# Esquematico_2022-08-20.net
KiCad netlist of a schematic drawn in Altium Designer
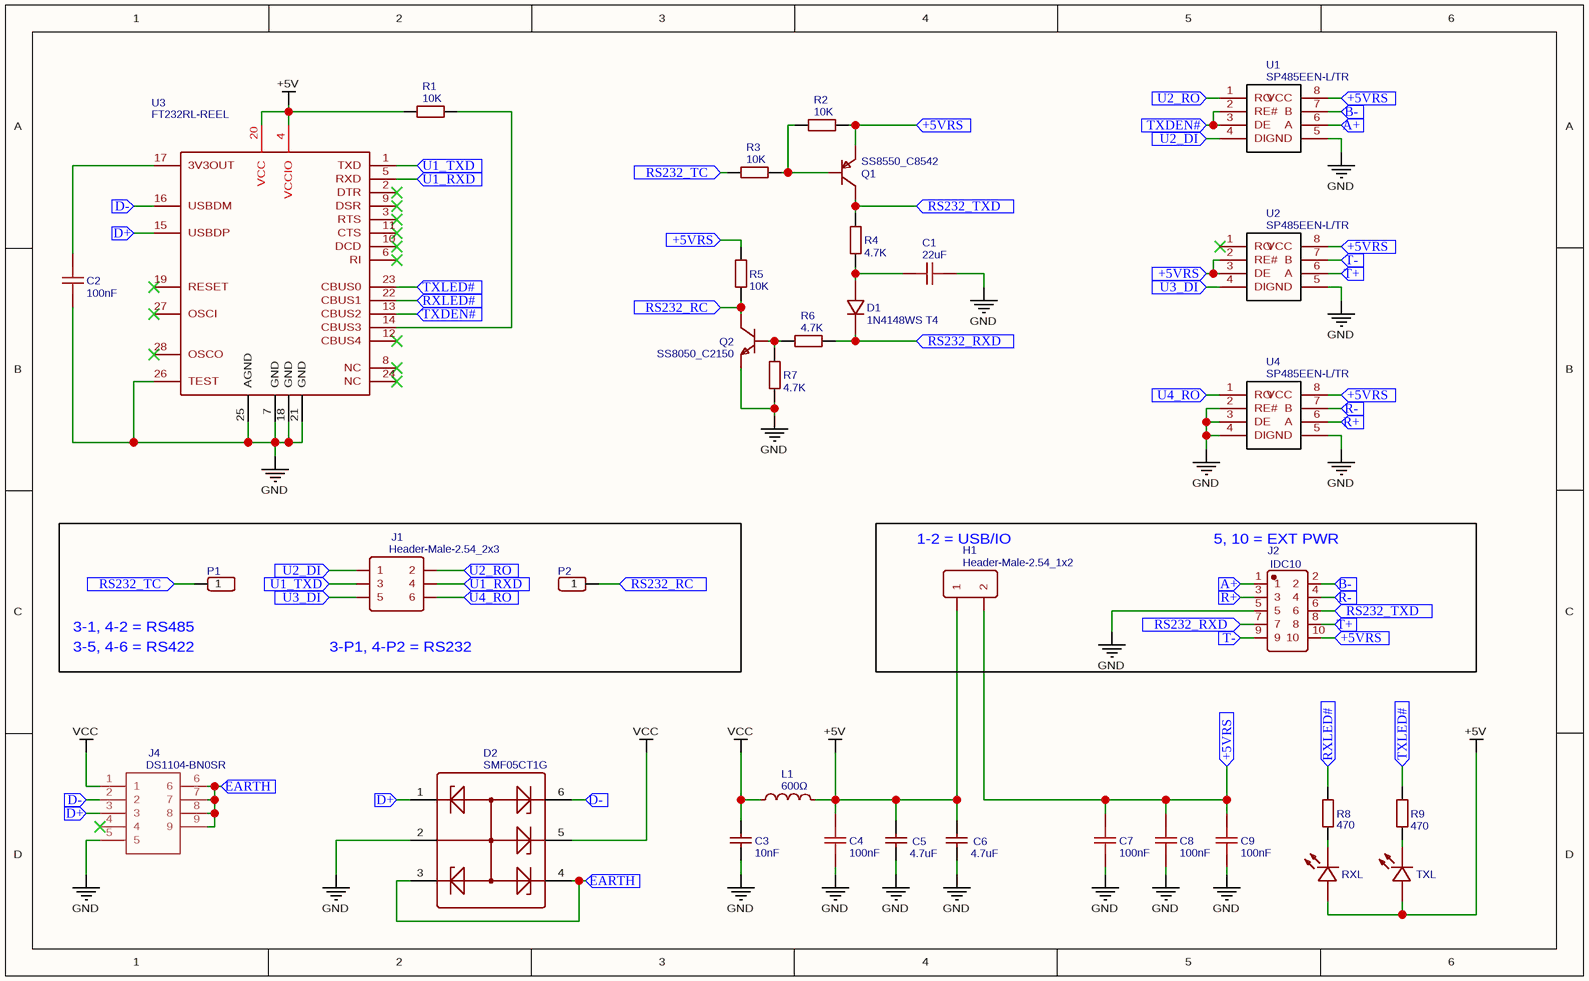
[diagram p0: Esquematico_2022-08-20.schdoc]

(export (version "E")
  (design (tool "Eeschema 10.0.6"))
  (components
    (comp (ref "C1")
      (value "22uF")
      (fields
        (field (name "BOM_MANUFACTURER PART") "CL21A226MAQNNNE")
        (field (name "BOM_SUPPLIER PART") "C45783")
      )
      (libsource (lib "altium-import") (part "root_0_22uF_"))
    )
    (comp (ref "C2")
      (value "100nF")
      (fields
        (field (name "BOM_MANUFACTURER PART") "CC0603KRX7R9BB104")
        (field (name "BOM_SUPPLIER PART") "C14663")
      )
      (libsource (lib "altium-import") (part "root_1_100nF_"))
    )
    (comp (ref "C3")
      (value "10nF")
      (fields
        (field (name "BOM_MANUFACTURER PART") "0603B103K500NT")
        (field (name "BOM_SUPPLIER PART") "C57112")
      )
      (libsource (lib "altium-import") (part "root_1_10nF_"))
    )
    (comp (ref "C4")
      (value "100nF")
      (fields
        (field (name "BOM_MANUFACTURER PART") "CC0603KRX7R9BB104")
        (field (name "BOM_SUPPLIER PART") "C14663")
      )
      (libsource (lib "altium-import") (part "root_1_100nF_"))
    )
    (comp (ref "C5")
      (value "4.7uF")
      (fields
        (field (name "BOM_MANUFACTURER PART") "CL10A475KO8NNNC")
        (field (name "BOM_SUPPLIER PART") "C19666")
      )
      (libsource (lib "altium-import") (part "root_1_4.7uF_"))
    )
    (comp (ref "C6")
      (value "4.7uF")
      (fields
        (field (name "BOM_MANUFACTURER PART") "CL10A475KO8NNNC")
        (field (name "BOM_SUPPLIER PART") "C19666")
      )
      (libsource (lib "altium-import") (part "root_1_4.7uF_"))
    )
    (comp (ref "C7")
      (value "100nF")
      (fields
        (field (name "BOM_MANUFACTURER PART") "CC0603KRX7R9BB104")
        (field (name "BOM_SUPPLIER PART") "C14663")
      )
      (libsource (lib "altium-import") (part "root_1_100nF_"))
    )
    (comp (ref "C8")
      (value "100nF")
      (fields
        (field (name "BOM_MANUFACTURER PART") "CC0603KRX7R9BB104")
        (field (name "BOM_SUPPLIER PART") "C14663")
      )
      (libsource (lib "altium-import") (part "root_1_100nF_"))
    )
    (comp (ref "C9")
      (value "100nF")
      (fields
        (field (name "BOM_MANUFACTURER PART") "CC0603KRX7R9BB104")
        (field (name "BOM_SUPPLIER PART") "C14663")
      )
      (libsource (lib "altium-import") (part "root_1_100nF_"))
    )
    (comp (ref "D1")
      (value "1N4148WS T4")
      (fields (field (name "BOM_SUPPLIER PART") "C2128"))
      (libsource (lib "altium-import") (part "root_1_1N4148WS T4_"))
    )
    (comp (ref "D2")
      (value "SMF05CT1G")
      (fields (field (name "BOM_SUPPLIER PART") "C15879"))
      (libsource (lib "altium-import") (part "root_0_SMF05CT1G_"))
    )
    (comp (ref "H1")
      (value "Header-Male-2.54_1x2")
      (fields (field (name "BOM_MANUFACTURER PART") "826629-2") (field (name "BOM_SUPPLIER PART") "C86471"))
      (libsource (lib "altium-import") (part "root_1_Header-Male-2.54_1x2_"))
    )
    (comp (ref "J1")
      (value "Header-Male-2.54_2x3")
      (fields (field (name "BOM_SUPPLIER PART") "C65114"))
      (libsource (lib "altium-import") (part "root_0_Header-Male-2.54_2x3_"))
    )
    (comp (ref "J2")
      (value "IDC10")
      (fields (field (name "CONTRIBUTOR") "romanlee"))
      (libsource (lib "altium-import") (part "root_0_IDC10_"))
    )
    (comp (ref "J4")
      (value "DS1104-BN0SR")
      (fields (field (name "CONTRIBUTOR") "kutsiarda"))
      (libsource (lib "altium-import") (part "root_0_DS1104-BN0SR_"))
    )
    (comp (ref "L1")
      (value "600Ω")
      (fields
        (field (name "BOM_MANUFACTURER PART") "GZ2012D601TF")
        (field (name "BOM_SUPPLIER PART") "C1017")
      )
      (libsource (lib "altium-import") (part "root_0_600Ω_"))
    )
    (comp (ref "P1")
      (value "Header-Male-2.54_1x1")
      (fields (field (name "BOM_SUPPLIER PART") "C81276"))
      (libsource (lib "altium-import") (part "root_0_Header-Male-2.54_1x1_"))
    )
    (comp (ref "P2")
      (value "Header-Male-2.54_1x1")
      (fields (field (name "BOM_SUPPLIER PART") "C81276"))
      (libsource (lib "altium-import") (part "root_2_Header-Male-2.54_1x1_"))
    )
    (comp (ref "Q1")
      (value "SS8550_C8542")
      (fields (field (name "BOM_MANUFACTURER PART") "SS8550") (field (name "BOM_SUPPLIER PART") "C8542"))
      (libsource (lib "altium-import") (part "root_0_SS8550_C8542_"))
    )
    (comp (ref "Q2")
      (value "SS8050_C2150")
      (fields (field (name "BOM_MANUFACTURER PART") "SS8050") (field (name "BOM_SUPPLIER PART") "C2150"))
      (libsource (lib "altium-import") (part "root_0_SS8050_C2150_"))
    )
    (comp (ref "R1")
      (value "10K")
      (fields
        (field (name "BOM_MANUFACTURER PART") "0603WAF1002T5E")
        (field (name "BOM_SUPPLIER PART") "C25804")
      )
      (libsource (lib "altium-import") (part "root_0_10K_"))
    )
    (comp (ref "R2")
      (value "10K")
      (fields
        (field (name "BOM_MANUFACTURER PART") "0603WAF1002T5E")
        (field (name "BOM_SUPPLIER PART") "C25804")
      )
      (libsource (lib "altium-import") (part "root_0_10K_"))
    )
    (comp (ref "R3")
      (value "10K")
      (fields
        (field (name "BOM_MANUFACTURER PART") "0603WAF1002T5E")
        (field (name "BOM_SUPPLIER PART") "C25804")
      )
      (libsource (lib "altium-import") (part "root_0_10K_"))
    )
    (comp (ref "R4")
      (value "4.7K")
      (fields
        (field (name "BOM_MANUFACTURER PART") "0603WAF4701T5E")
        (field (name "BOM_SUPPLIER PART") "C23162")
      )
      (libsource (lib "altium-import") (part "root_1_4.7K_"))
    )
    (comp (ref "R5")
      (value "10K")
      (fields
        (field (name "BOM_MANUFACTURER PART") "0603WAF1002T5E")
        (field (name "BOM_SUPPLIER PART") "C25804")
      )
      (libsource (lib "altium-import") (part "root_1_10K_"))
    )
    (comp (ref "R6")
      (value "4.7K")
      (fields
        (field (name "BOM_MANUFACTURER PART") "0603WAF4701T5E")
        (field (name "BOM_SUPPLIER PART") "C23162")
      )
      (libsource (lib "altium-import") (part "root_2_4.7K_"))
    )
    (comp (ref "R7")
      (value "4.7K")
      (fields
        (field (name "BOM_MANUFACTURER PART") "0603WAF4701T5E")
        (field (name "BOM_SUPPLIER PART") "C23162")
      )
      (libsource (lib "altium-import") (part "root_3_4.7K_"))
    )
    (comp (ref "R8")
      (value "470")
      (fields
        (field (name "BOM_MANUFACTURER PART") "0603WAF4700T5E")
        (field (name "BOM_SUPPLIER PART") "C23179")
      )
      (libsource (lib "altium-import") (part "root_1_470_"))
    )
    (comp (ref "R9")
      (value "470")
      (fields
        (field (name "BOM_MANUFACTURER PART") "0603WAF4700T5E")
        (field (name "BOM_SUPPLIER PART") "C23179")
      )
      (libsource (lib "altium-import") (part "root_3_470_"))
    )
    (comp (ref "RXL")
      (value "RXL")
      (fields
        (field (name "BOM_MANUFACTURER PART") "0603White light")
        (field (name "BOM_SUPPLIER PART") "C2290")
      )
      (libsource (lib "altium-import") (part "root_1_RXL_"))
    )
    (comp (ref "TXL")
      (value "TXL")
      (fields (field (name "BOM_MANUFACTURER PART") "KT-0603R") (field (name "BOM_SUPPLIER PART") "C2286"))
      (libsource (lib "altium-import") (part "root_3_TXL_"))
    )
    (comp (ref "U1")
      (value "SP485EEN-L/TR")
      (fields (field (name "BOM_SUPPLIER PART") "C6855"))
      (libsource (lib "altium-import") (part "root_0_SP485EEN-L/TR_"))
    )
    (comp (ref "U2")
      (value "SP485EEN-L/TR")
      (fields (field (name "BOM_SUPPLIER PART") "C6855"))
      (libsource (lib "altium-import") (part "root_0_SP485EEN-L/TR_"))
    )
    (comp (ref "U3")
      (value "FT232RL-REEL")
      (fields (field (name "BOM_SUPPLIER PART") "C8690"))
      (libsource (lib "altium-import") (part "root_0_FT232RL-REEL_"))
    )
    (comp (ref "U4")
      (value "SP485EEN-L/TR")
      (fields (field (name "BOM_SUPPLIER PART") "C6855"))
      (libsource (lib "altium-import") (part "root_0_SP485EEN-L/TR_"))
    )
  )
  (nets
    (net (code "1") (name "+5V") (class "Default")
      (node (ref "C4") (pin "2") (pinfunction "2_2") (pintype "passive"))
      (node (ref "C5") (pin "2") (pinfunction "2_2") (pintype "passive"))
      (node (ref "C6") (pin "2") (pinfunction "2_2") (pintype "passive"))
      (node (ref "H1") (pin "1") (pinfunction "1_1") (pintype "passive"))
      (node (ref "L1") (pin "2") (pinfunction "2_2") (pintype "passive"))
      (node (ref "R1") (pin "1") (pinfunction "1_1") (pintype "passive"))
      (node (ref "RXL") (pin "1") (pinfunction "A_1") (pintype "passive"))
      (node (ref "TXL") (pin "1") (pinfunction "A_1") (pintype "passive"))
      (node (ref "U3") (pin "20") (pinfunction "VCC_20") (pintype "passive"))
      (node (ref "U3") (pin "4") (pinfunction "VCCIO_4") (pintype "passive"))
    )
    (net (code "2") (name "/+5VRS") (class "Default")
      (node (ref "C7") (pin "2") (pinfunction "2_2") (pintype "passive"))
      (node (ref "C8") (pin "2") (pinfunction "2_2") (pintype "passive"))
      (node (ref "C9") (pin "2") (pinfunction "2_2") (pintype "passive"))
      (node (ref "H1") (pin "2") (pinfunction "2_2") (pintype "passive"))
      (node (ref "J2") (pin "10") (pinfunction "10_10") (pintype "passive"))
      (node (ref "Q1") (pin "2") (pinfunction "E_2") (pintype "passive"))
      (node (ref "R2") (pin "2") (pinfunction "2_2") (pintype "passive"))
      (node (ref "R5") (pin "2") (pinfunction "2_2") (pintype "passive"))
      (node (ref "U1") (pin "8") (pinfunction "VCC_8") (pintype "passive"))
      (node (ref "U2") (pin "2") (pinfunction "RE#_2") (pintype "passive"))
      (node (ref "U2") (pin "3") (pinfunction "DE_3") (pintype "passive"))
      (node (ref "U2") (pin "8") (pinfunction "VCC_8") (pintype "passive"))
      (node (ref "U4") (pin "8") (pinfunction "VCC_8") (pintype "passive"))
    )
    (net (code "3") (name "/A+") (class "Default")
      (node (ref "J2") (pin "1") (pinfunction "1_1") (pintype "passive"))
      (node (ref "U1") (pin "6") (pinfunction "A_6") (pintype "passive"))
    )
    (net (code "4") (name "/B-") (class "Default")
      (node (ref "J2") (pin "2") (pinfunction "2_2") (pintype "passive"))
      (node (ref "U1") (pin "7") (pinfunction "B_7") (pintype "passive"))
    )
    (net (code "5") (name "/D+") (class "Default")
      (node (ref "D2") (pin "1") (pinfunction "1_1") (pintype "passive"))
      (node (ref "J4") (pin "3") (pinfunction "3_3") (pintype "passive"))
      (node (ref "U3") (pin "15") (pinfunction "USBDP_15") (pintype "passive"))
    )
    (net (code "6") (name "/D-") (class "Default")
      (node (ref "D2") (pin "6") (pinfunction "6_6") (pintype "passive"))
      (node (ref "J4") (pin "2") (pinfunction "2_2") (pintype "passive"))
      (node (ref "U3") (pin "16") (pinfunction "USBDM_16") (pintype "passive"))
    )
    (net (code "7") (name "/EARTH") (class "Default")
      (node (ref "D2") (pin "3") (pinfunction "3_3") (pintype "passive"))
      (node (ref "D2") (pin "4") (pinfunction "4_4") (pintype "passive"))
      (node (ref "J4") (pin "6") (pinfunction "6_6") (pintype "passive"))
      (node (ref "J4") (pin "7") (pinfunction "7_7") (pintype "passive"))
      (node (ref "J4") (pin "8") (pinfunction "8_8") (pintype "passive"))
      (node (ref "J4") (pin "9") (pinfunction "9_9") (pintype "passive"))
    )
    (net (code "8") (name "/R+") (class "Default")
      (node (ref "J2") (pin "3") (pinfunction "3_3") (pintype "passive"))
      (node (ref "U4") (pin "6") (pinfunction "A_6") (pintype "passive"))
    )
    (net (code "9") (name "/R-") (class "Default")
      (node (ref "J2") (pin "4") (pinfunction "4_4") (pintype "passive"))
      (node (ref "U4") (pin "7") (pinfunction "B_7") (pintype "passive"))
    )
    (net (code "10") (name "/RS232_RC") (class "Default")
      (node (ref "P2") (pin "1") (pinfunction "1_1") (pintype "passive"))
      (node (ref "Q2") (pin "3") (pinfunction "C_3") (pintype "passive"))
      (node (ref "R5") (pin "1") (pinfunction "1_1") (pintype "passive"))
    )
    (net (code "11") (name "/RS232_RXD") (class "Default")
      (node (ref "D1") (pin "1") (pinfunction "K_1") (pintype "passive"))
      (node (ref "J2") (pin "7") (pinfunction "7_7") (pintype "passive"))
      (node (ref "R6") (pin "1") (pinfunction "1_1") (pintype "passive"))
    )
    (net (code "12") (name "/RS232_TC") (class "Default")
      (node (ref "P1") (pin "1") (pinfunction "1_1") (pintype "passive"))
      (node (ref "R3") (pin "1") (pinfunction "1_1") (pintype "passive"))
    )
    (net (code "13") (name "/RS232_TXD") (class "Default")
      (node (ref "J2") (pin "6") (pinfunction "6_6") (pintype "passive"))
      (node (ref "Q1") (pin "3") (pinfunction "C_3") (pintype "passive"))
      (node (ref "R4") (pin "2") (pinfunction "2_2") (pintype "passive"))
    )
    (net (code "14") (name "/RXLED#") (class "Default")
      (node (ref "R8") (pin "2") (pinfunction "2_2") (pintype "passive"))
      (node (ref "U3") (pin "22") (pinfunction "CBUS1_22") (pintype "passive"))
    )
    (net (code "15") (name "/T+") (class "Default")
      (node (ref "J2") (pin "8") (pinfunction "8_8") (pintype "passive"))
      (node (ref "U2") (pin "6") (pinfunction "A_6") (pintype "passive"))
    )
    (net (code "16") (name "/T-") (class "Default")
      (node (ref "J2") (pin "9") (pinfunction "9_9") (pintype "passive"))
      (node (ref "U2") (pin "7") (pinfunction "B_7") (pintype "passive"))
    )
    (net (code "17") (name "/TXDEN#") (class "Default")
      (node (ref "U1") (pin "2") (pinfunction "RE#_2") (pintype "passive"))
      (node (ref "U1") (pin "3") (pinfunction "DE_3") (pintype "passive"))
      (node (ref "U3") (pin "13") (pinfunction "CBUS2_13") (pintype "passive"))
    )
    (net (code "18") (name "/TXLED#") (class "Default")
      (node (ref "R9") (pin "1") (pinfunction "1_1") (pintype "passive"))
      (node (ref "U3") (pin "23") (pinfunction "CBUS0_23") (pintype "passive"))
    )
    (net (code "19") (name "/U1_RXD") (class "Default")
      (node (ref "J1") (pin "4") (pinfunction "4_4") (pintype "passive"))
      (node (ref "U3") (pin "5") (pinfunction "RXD_5") (pintype "passive"))
    )
    (net (code "20") (name "/U1_TXD") (class "Default")
      (node (ref "J1") (pin "3") (pinfunction "3_3") (pintype "passive"))
      (node (ref "U3") (pin "1") (pinfunction "TXD_1") (pintype "passive"))
    )
    (net (code "21") (name "/U2_DI") (class "Default")
      (node (ref "J1") (pin "1") (pinfunction "1_1") (pintype "passive"))
      (node (ref "U1") (pin "4") (pinfunction "DI_4") (pintype "passive"))
    )
    (net (code "22") (name "/U2_RO") (class "Default")
      (node (ref "J1") (pin "2") (pinfunction "2_2") (pintype "passive"))
      (node (ref "U1") (pin "1") (pinfunction "RO_1") (pintype "passive"))
    )
    (net (code "23") (name "/U3_DI") (class "Default")
      (node (ref "J1") (pin "5") (pinfunction "5_5") (pintype "passive"))
      (node (ref "U2") (pin "4") (pinfunction "DI_4") (pintype "passive"))
    )
    (net (code "24") (name "/U4_RO") (class "Default")
      (node (ref "J1") (pin "6") (pinfunction "6_6") (pintype "passive"))
      (node (ref "U4") (pin "1") (pinfunction "RO_1") (pintype "passive"))
    )
    (net (code "25") (name "GND") (class "Default")
      (node (ref "C1") (pin "2") (pinfunction "2_2") (pintype "passive"))
      (node (ref "C2") (pin "1") (pinfunction "1_1") (pintype "passive"))
      (node (ref "C3") (pin "1") (pinfunction "1_1") (pintype "passive"))
      (node (ref "C4") (pin "1") (pinfunction "1_1") (pintype "passive"))
      (node (ref "C5") (pin "1") (pinfunction "1_1") (pintype "passive"))
      (node (ref "C6") (pin "1") (pinfunction "1_1") (pintype "passive"))
      (node (ref "C7") (pin "1") (pinfunction "1_1") (pintype "passive"))
      (node (ref "C8") (pin "1") (pinfunction "1_1") (pintype "passive"))
      (node (ref "C9") (pin "1") (pinfunction "1_1") (pintype "passive"))
      (node (ref "D2") (pin "2") (pinfunction "2_2") (pintype "passive"))
      (node (ref "J2") (pin "5") (pinfunction "5_5") (pintype "passive"))
      (node (ref "J4") (pin "5") (pinfunction "5_5") (pintype "passive"))
      (node (ref "Q2") (pin "2") (pinfunction "E_2") (pintype "passive"))
      (node (ref "R7") (pin "2") (pinfunction "2_2") (pintype "passive"))
      (node (ref "U1") (pin "5") (pinfunction "GND_5") (pintype "passive"))
      (node (ref "U2") (pin "5") (pinfunction "GND_5") (pintype "passive"))
      (node (ref "U3") (pin "18") (pinfunction "GND_18") (pintype "passive"))
      (node (ref "U3") (pin "21") (pinfunction "GND_21") (pintype "passive"))
      (node (ref "U3") (pin "25") (pinfunction "AGND_25") (pintype "passive"))
      (node (ref "U3") (pin "26") (pinfunction "TEST_26") (pintype "passive"))
      (node (ref "U3") (pin "7") (pinfunction "GND_7") (pintype "passive"))
      (node (ref "U4") (pin "2") (pinfunction "RE#_2") (pintype "passive"))
      (node (ref "U4") (pin "3") (pinfunction "DE_3") (pintype "passive"))
      (node (ref "U4") (pin "4") (pinfunction "DI_4") (pintype "passive"))
      (node (ref "U4") (pin "5") (pinfunction "GND_5") (pintype "passive"))
    )
    (net (code "26") (name "Net-(D1-A)") (class "Default")
      (node (ref "C1") (pin "1") (pinfunction "1_1") (pintype "passive"))
      (node (ref "D1") (pin "2") (pinfunction "A_2") (pintype "passive"))
      (node (ref "R4") (pin "1") (pinfunction "1_1") (pintype "passive"))
    )
    (net (code "27") (name "Net-(Q1-B)") (class "Default")
      (node (ref "Q1") (pin "1") (pinfunction "B_1") (pintype "passive"))
      (node (ref "R2") (pin "1") (pinfunction "1_1") (pintype "passive"))
      (node (ref "R3") (pin "2") (pinfunction "2_2") (pintype "passive"))
    )
    (net (code "28") (name "Net-(Q2-B)") (class "Default")
      (node (ref "Q2") (pin "1") (pinfunction "B_1") (pintype "passive"))
      (node (ref "R6") (pin "2") (pinfunction "2_2") (pintype "passive"))
      (node (ref "R7") (pin "1") (pinfunction "1_1") (pintype "passive"))
    )
    (net (code "29") (name "Net-(RXL-K)") (class "Default")
      (node (ref "R8") (pin "1") (pinfunction "1_1") (pintype "passive"))
      (node (ref "RXL") (pin "2") (pinfunction "K_2") (pintype "passive"))
    )
    (net (code "30") (name "Net-(TXL-K)") (class "Default")
      (node (ref "R9") (pin "2") (pinfunction "2_2") (pintype "passive"))
      (node (ref "TXL") (pin "2") (pinfunction "K_2") (pintype "passive"))
    )
    (net (code "31") (name "Net-(U3-3V3OUT)") (class "Default")
      (node (ref "C2") (pin "2") (pinfunction "2_2") (pintype "passive"))
      (node (ref "U3") (pin "17") (pinfunction "3V3OUT_17") (pintype "passive"))
    )
    (net (code "32") (name "Net-(U3-CBUS3)") (class "Default")
      (node (ref "R1") (pin "2") (pinfunction "2_2") (pintype "passive"))
      (node (ref "U3") (pin "14") (pinfunction "CBUS3_14") (pintype "passive"))
    )
    (net (code "33") (name "VCC") (class "Default")
      (node (ref "C3") (pin "2") (pinfunction "2_2") (pintype "passive"))
      (node (ref "D2") (pin "5") (pinfunction "5_5") (pintype "passive"))
      (node (ref "J4") (pin "1") (pinfunction "1_1") (pintype "passive"))
      (node (ref "L1") (pin "1") (pinfunction "1_1") (pintype "passive"))
    )
    (net (code "34") (name "unconnected-(J4-Pad4)") (class "Default")
      (node (ref "J4") (pin "4") (pinfunction "4_4") (pintype "passive+no_connect"))
    )
    (net (code "35") (name "unconnected-(U2-RO-Pad1)") (class "Default")
      (node (ref "U2") (pin "1") (pinfunction "RO_1") (pintype "passive+no_connect"))
    )
    (net (code "36") (name "unconnected-(U3-CBUS4-Pad12)") (class "Default")
      (node (ref "U3") (pin "12") (pinfunction "CBUS4_12") (pintype "passive+no_connect"))
    )
    (net (code "37") (name "unconnected-(U3-CTS-Pad11)") (class "Default")
      (node (ref "U3") (pin "11") (pinfunction "CTS_11") (pintype "passive+no_connect"))
    )
    (net (code "38") (name "unconnected-(U3-DCD-Pad10)") (class "Default")
      (node (ref "U3") (pin "10") (pinfunction "DCD_10") (pintype "passive+no_connect"))
    )
    (net (code "39") (name "unconnected-(U3-DSR-Pad9)") (class "Default")
      (node (ref "U3") (pin "9") (pinfunction "DSR_9") (pintype "passive+no_connect"))
    )
    (net (code "40") (name "unconnected-(U3-DTR-Pad2)") (class "Default")
      (node (ref "U3") (pin "2") (pinfunction "DTR_2") (pintype "passive+no_connect"))
    )
    (net (code "41") (name "unconnected-(U3-NC-Pad8)") (class "Default")
      (node (ref "U3") (pin "8") (pinfunction "NC_8") (pintype "passive+no_connect"))
    )
    (net (code "42") (name "unconnected-(U3-NC-Pad24)") (class "Default")
      (node (ref "U3") (pin "24") (pinfunction "NC_24") (pintype "passive+no_connect"))
    )
    (net (code "43") (name "unconnected-(U3-OSCI-Pad27)") (class "Default")
      (node (ref "U3") (pin "27") (pinfunction "OSCI_27") (pintype "passive+no_connect"))
    )
    (net (code "44") (name "unconnected-(U3-OSCO-Pad28)") (class "Default")
      (node (ref "U3") (pin "28") (pinfunction "OSCO_28") (pintype "passive+no_connect"))
    )
    (net (code "45") (name "unconnected-(U3-RESET-Pad19)") (class "Default")
      (node (ref "U3") (pin "19") (pinfunction "RESET_19") (pintype "passive+no_connect"))
    )
    (net (code "46") (name "unconnected-(U3-RI-Pad6)") (class "Default")
      (node (ref "U3") (pin "6") (pinfunction "RI_6") (pintype "passive+no_connect"))
    )
    (net (code "47") (name "unconnected-(U3-RTS-Pad3)") (class "Default")
      (node (ref "U3") (pin "3") (pinfunction "RTS_3") (pintype "passive+no_connect"))
    )
  )
)
